# display.net
KiCad netlist of a schematic drawn in EAGLE
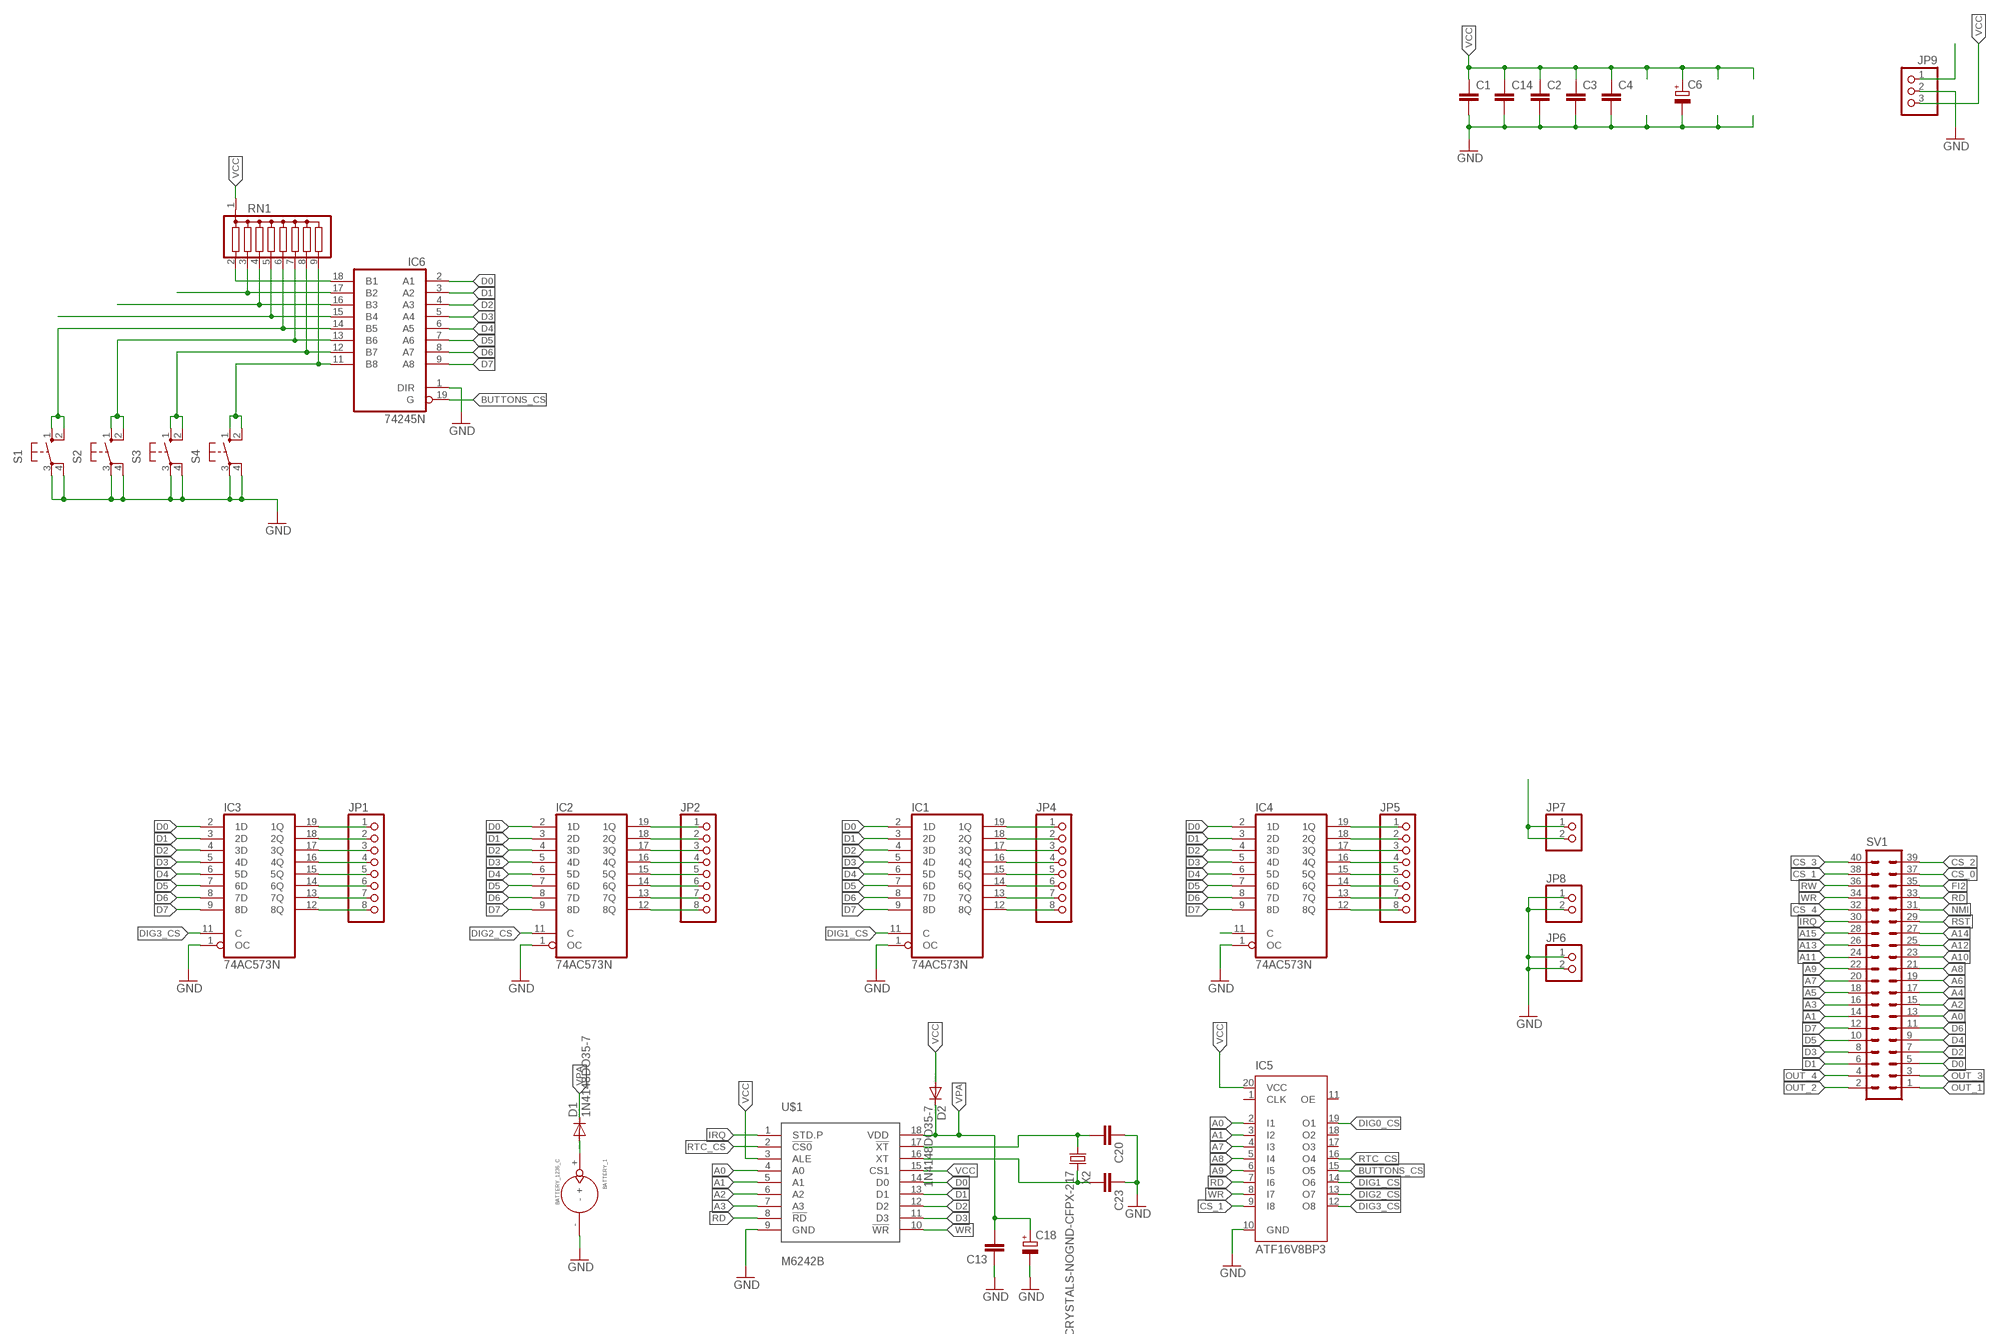
[diagram p0: schematic, sheet 1]

(export (version "E")
  (design (tool "Eeschema 10.0.6"))
  (components
    (comp (ref "BATTERY_1")
      (value "BATTERY_1236_C")
      (footprint "eagle-import:BATTERY_1236_C")
      (libsource (lib "eagle-import") (part "BATTERY_1236_C"))
    )
    (comp (ref "C1")
      (value "C-EUC1206")
      (footprint "eagle-import:C1206")
      (libsource (lib "eagle-import") (part "C-EUC1206"))
    )
    (comp (ref "C2")
      (value "C-EUC1206")
      (footprint "eagle-import:C1206")
      (libsource (lib "eagle-import") (part "C-EUC1206"))
    )
    (comp (ref "C3")
      (value "C-EUC1206")
      (footprint "eagle-import:C1206")
      (libsource (lib "eagle-import") (part "C-EUC1206"))
    )
    (comp (ref "C4")
      (value "C-EUC1206")
      (footprint "eagle-import:C1206")
      (libsource (lib "eagle-import") (part "C-EUC1206"))
    )
    (comp (ref "C6")
      (value "CPOL-EUSMCD")
      (footprint "eagle-import:SMC_D")
      (libsource (lib "eagle-import") (part "CPOL-EUSMCD"))
    )
    (comp (ref "C13")
      (value "C-EUC0603")
      (footprint "eagle-import:C0603")
      (libsource (lib "eagle-import") (part "C-EUC0603"))
    )
    (comp (ref "C14")
      (value "C-EUC1206")
      (footprint "eagle-import:C1206")
      (libsource (lib "eagle-import") (part "C-EUC1206"))
    )
    (comp (ref "C18")
      (value "CPOL-EUSMCB")
      (footprint "eagle-import:SMC_B")
      (libsource (lib "eagle-import") (part "CPOL-EUSMCB"))
    )
    (comp (ref "C20")
      (value "C-EUC0603")
      (footprint "eagle-import:C0603")
      (libsource (lib "eagle-import") (part "C-EUC0603"))
    )
    (comp (ref "C23")
      (value "C-EUC0603")
      (footprint "eagle-import:C0603")
      (libsource (lib "eagle-import") (part "C-EUC0603"))
    )
    (comp (ref "D1")
      (value "1N4148DO35-7")
      (footprint "eagle-import:DO35-7")
      (libsource (lib "eagle-import") (part "1N4148DO35-7"))
    )
    (comp (ref "D2")
      (value "1N4148DO35-7")
      (footprint "eagle-import:DO35-7")
      (libsource (lib "eagle-import") (part "1N4148DO35-7"))
    )
    (comp (ref "IC1")
      (value "74AC573N")
      (footprint "eagle-import:DIL20")
      (libsource (lib "eagle-import") (part "74573NAC"))
    )
    (comp (ref "IC2")
      (value "74AC573N")
      (footprint "eagle-import:DIL20")
      (libsource (lib "eagle-import") (part "74573NAC"))
    )
    (comp (ref "IC3")
      (value "74AC573N")
      (footprint "eagle-import:DIL20")
      (libsource (lib "eagle-import") (part "74573NAC"))
    )
    (comp (ref "IC4")
      (value "74AC573N")
      (footprint "eagle-import:DIL20")
      (libsource (lib "eagle-import") (part "74573NAC"))
    )
    (comp (ref "IC5")
      (value "ATF16V8BP3")
      (footprint "eagle-import:DIL20")
      (fields (field (name "MPN") "ATF16V8CZ-15PU"))
      (libsource (lib "eagle-import") (part "ATF16V8BP3"))
    )
    (comp (ref "IC6")
      (value "74245N")
      (footprint "eagle-import:DIL20")
      (libsource (lib "eagle-import") (part "74245NLS"))
    )
    (comp (ref "JP1")
      (value "PINHD-1X8")
      (footprint "eagle-import:1X08")
      (libsource (lib "eagle-import") (part "PINHD-1X8"))
    )
    (comp (ref "JP2")
      (value "PINHD-1X8")
      (footprint "eagle-import:1X08")
      (libsource (lib "eagle-import") (part "PINHD-1X8"))
    )
    (comp (ref "JP4")
      (value "PINHD-1X8")
      (footprint "eagle-import:1X08")
      (libsource (lib "eagle-import") (part "PINHD-1X8"))
    )
    (comp (ref "JP5")
      (value "PINHD-1X8")
      (footprint "eagle-import:1X08")
      (libsource (lib "eagle-import") (part "PINHD-1X8"))
    )
    (comp (ref "JP6")
      (value "PINHD-1X2")
      (footprint "eagle-import:1X02")
      (libsource (lib "eagle-import") (part "PINHD-1X2"))
    )
    (comp (ref "JP7")
      (value "PINHD-1X2")
      (footprint "eagle-import:1X02")
      (libsource (lib "eagle-import") (part "PINHD-1X2"))
    )
    (comp (ref "JP8")
      (value "PINHD-1X2")
      (footprint "eagle-import:1X02")
      (libsource (lib "eagle-import") (part "PINHD-1X2"))
    )
    (comp (ref "JP9")
      (value "PINHD-1X3/90")
      (footprint "eagle-import:1X03_90")
      (libsource (lib "eagle-import") (part "PINHD-1X3/90"))
    )
    (comp (ref "RN1")
      (value "G08R")
      (footprint "eagle-import:SIL9")
      (libsource (lib "eagle-import") (part "G08R"))
    )
    (comp (ref "S1")
      (value "40-XX")
      (footprint "eagle-import:B3F-40XX")
      (fields (field (name "MF") "OMRON COMPONENTS USA") (field (name "MPN") "B3F-4000"))
      (libsource (lib "eagle-import") (part "40-XX"))
    )
    (comp (ref "S2")
      (value "40-XX")
      (footprint "eagle-import:B3F-40XX")
      (fields (field (name "MF") "OMRON COMPONENTS USA") (field (name "MPN") "B3F-4000"))
      (libsource (lib "eagle-import") (part "40-XX"))
    )
    (comp (ref "S3")
      (value "40-XX")
      (footprint "eagle-import:B3F-40XX")
      (fields (field (name "MF") "OMRON COMPONENTS USA") (field (name "MPN") "B3F-4000"))
      (libsource (lib "eagle-import") (part "40-XX"))
    )
    (comp (ref "S4")
      (value "40-XX")
      (footprint "eagle-import:B3F-40XX")
      (fields (field (name "MF") "OMRON COMPONENTS USA") (field (name "MPN") "B3F-4000"))
      (libsource (lib "eagle-import") (part "40-XX"))
    )
    (comp (ref "SV1")
      (value "ML40L")
      (footprint "eagle-import:ML40L")
      (libsource (lib "eagle-import") (part "ML40L"))
    )
    (comp (ref "U$1")
      (value "M6242B")
      (footprint "eagle-import:DIL18")
      (libsource (lib "eagle-import") (part "M6242B"))
    )
    (comp (ref "X2")
      (value "CRYSTALS-NOGND-CFPX-217")
      (footprint "eagle-import:3.2X1.5-2-PAD")
      (libsource (lib "eagle-import") (part "CRYSTALS-NOGND-CFPX-217"))
    )
  )
  (nets
    (net (code "1") (name "/9V") (class "Default")
      (node (ref "JP7") (pin "1") (pinfunction "1_1") (pintype "passive"))
      (node (ref "JP7") (pin "2") (pinfunction "2_2") (pintype "passive"))
      (node (ref "JP9") (pin "1") (pinfunction "1_1") (pintype "passive"))
    )
    (net (code "2") (name "A0") (class "Default")
      (node (ref "IC5") (pin "2") (pinfunction "I1_2") (pintype "input"))
      (node (ref "SV1") (pin "13") (pinfunction "13_13") (pintype "passive"))
      (node (ref "U$1") (pin "4") (pinfunction "A0_4") (pintype "bidirectional"))
    )
    (net (code "3") (name "A1") (class "Default")
      (node (ref "IC5") (pin "3") (pinfunction "I2_3") (pintype "input"))
      (node (ref "SV1") (pin "14") (pinfunction "14_14") (pintype "passive"))
      (node (ref "U$1") (pin "5") (pinfunction "A1_5") (pintype "bidirectional"))
    )
    (net (code "4") (name "A2") (class "Default")
      (node (ref "SV1") (pin "15") (pinfunction "15_15") (pintype "passive"))
      (node (ref "U$1") (pin "6") (pinfunction "A2_6") (pintype "bidirectional"))
    )
    (net (code "5") (name "A3") (class "Default")
      (node (ref "SV1") (pin "16") (pinfunction "16_16") (pintype "passive"))
      (node (ref "U$1") (pin "7") (pinfunction "A3_7") (pintype "bidirectional"))
    )
    (net (code "6") (name "A4") (class "Default")
      (node (ref "SV1") (pin "17") (pinfunction "17_17") (pintype "passive"))
    )
    (net (code "7") (name "A5") (class "Default")
      (node (ref "SV1") (pin "18") (pinfunction "18_18") (pintype "passive"))
    )
    (net (code "8") (name "A6") (class "Default")
      (node (ref "SV1") (pin "19") (pinfunction "19_19") (pintype "passive"))
    )
    (net (code "9") (name "A7") (class "Default")
      (node (ref "IC5") (pin "4") (pinfunction "I3_4") (pintype "input"))
      (node (ref "SV1") (pin "20") (pinfunction "20_20") (pintype "passive"))
    )
    (net (code "10") (name "A8") (class "Default")
      (node (ref "IC5") (pin "5") (pinfunction "I4_5") (pintype "input"))
      (node (ref "SV1") (pin "21") (pinfunction "21_21") (pintype "passive"))
    )
    (net (code "11") (name "A9") (class "Default")
      (node (ref "IC5") (pin "6") (pinfunction "I5_6") (pintype "input"))
      (node (ref "SV1") (pin "22") (pinfunction "22_22") (pintype "passive"))
    )
    (net (code "12") (name "A10") (class "Default")
      (node (ref "SV1") (pin "23") (pinfunction "23_23") (pintype "passive"))
    )
    (net (code "13") (name "A11") (class "Default")
      (node (ref "SV1") (pin "24") (pinfunction "24_24") (pintype "passive"))
    )
    (net (code "14") (name "A12") (class "Default")
      (node (ref "SV1") (pin "25") (pinfunction "25_25") (pintype "passive"))
    )
    (net (code "15") (name "A13") (class "Default")
      (node (ref "SV1") (pin "26") (pinfunction "26_26") (pintype "passive"))
    )
    (net (code "16") (name "A14") (class "Default")
      (node (ref "SV1") (pin "27") (pinfunction "27_27") (pintype "passive"))
    )
    (net (code "17") (name "A15") (class "Default")
      (node (ref "SV1") (pin "28") (pinfunction "28_28") (pintype "passive"))
    )
    (net (code "18") (name "BUTTONS_CS") (class "Default")
      (node (ref "IC5") (pin "15") (pinfunction "O5_15") (pintype "output"))
      (node (ref "IC6") (pin "19") (pinfunction "G_19") (pintype "input"))
    )
    (net (code "19") (name "CS_0") (class "Default")
      (node (ref "SV1") (pin "37") (pinfunction "37_37") (pintype "passive"))
    )
    (net (code "20") (name "CS_1") (class "Default")
      (node (ref "IC5") (pin "9") (pinfunction "I8_9") (pintype "input"))
      (node (ref "SV1") (pin "38") (pinfunction "38_38") (pintype "passive"))
    )
    (net (code "21") (name "CS_2") (class "Default")
      (node (ref "SV1") (pin "39") (pinfunction "39_39") (pintype "passive"))
    )
    (net (code "22") (name "CS_3") (class "Default")
      (node (ref "SV1") (pin "40") (pinfunction "40_40") (pintype "passive"))
    )
    (net (code "23") (name "CS_4") (class "Default")
      (node (ref "SV1") (pin "32") (pinfunction "32_32") (pintype "passive"))
    )
    (net (code "24") (name "D0") (class "Default")
      (node (ref "IC1") (pin "2") (pinfunction "1D_2") (pintype "input"))
      (node (ref "IC2") (pin "2") (pinfunction "1D_2") (pintype "input"))
      (node (ref "IC3") (pin "2") (pinfunction "1D_2") (pintype "input"))
      (node (ref "IC4") (pin "2") (pinfunction "1D_2") (pintype "input"))
      (node (ref "IC6") (pin "2") (pinfunction "A1_2") (pintype "bidirectional"))
      (node (ref "SV1") (pin "5") (pinfunction "5_5") (pintype "passive"))
      (node (ref "U$1") (pin "14") (pinfunction "D0_14") (pintype "bidirectional"))
    )
    (net (code "25") (name "D1") (class "Default")
      (node (ref "IC1") (pin "3") (pinfunction "2D_3") (pintype "input"))
      (node (ref "IC2") (pin "3") (pinfunction "2D_3") (pintype "input"))
      (node (ref "IC3") (pin "3") (pinfunction "2D_3") (pintype "input"))
      (node (ref "IC4") (pin "3") (pinfunction "2D_3") (pintype "input"))
      (node (ref "IC6") (pin "3") (pinfunction "A2_3") (pintype "bidirectional"))
      (node (ref "SV1") (pin "6") (pinfunction "6_6") (pintype "passive"))
      (node (ref "U$1") (pin "13") (pinfunction "D1_13") (pintype "bidirectional"))
    )
    (net (code "26") (name "D2") (class "Default")
      (node (ref "IC1") (pin "4") (pinfunction "3D_4") (pintype "input"))
      (node (ref "IC2") (pin "4") (pinfunction "3D_4") (pintype "input"))
      (node (ref "IC3") (pin "4") (pinfunction "3D_4") (pintype "input"))
      (node (ref "IC4") (pin "4") (pinfunction "3D_4") (pintype "input"))
      (node (ref "IC6") (pin "4") (pinfunction "A3_4") (pintype "bidirectional"))
      (node (ref "SV1") (pin "7") (pinfunction "7_7") (pintype "passive"))
      (node (ref "U$1") (pin "12") (pinfunction "D2_12") (pintype "bidirectional"))
    )
    (net (code "27") (name "D3") (class "Default")
      (node (ref "IC1") (pin "5") (pinfunction "4D_5") (pintype "input"))
      (node (ref "IC2") (pin "5") (pinfunction "4D_5") (pintype "input"))
      (node (ref "IC3") (pin "5") (pinfunction "4D_5") (pintype "input"))
      (node (ref "IC4") (pin "5") (pinfunction "4D_5") (pintype "input"))
      (node (ref "IC6") (pin "5") (pinfunction "A4_5") (pintype "bidirectional"))
      (node (ref "SV1") (pin "8") (pinfunction "8_8") (pintype "passive"))
      (node (ref "U$1") (pin "11") (pinfunction "D3_11") (pintype "bidirectional"))
    )
    (net (code "28") (name "D4") (class "Default")
      (node (ref "IC1") (pin "6") (pinfunction "5D_6") (pintype "input"))
      (node (ref "IC2") (pin "6") (pinfunction "5D_6") (pintype "input"))
      (node (ref "IC3") (pin "6") (pinfunction "5D_6") (pintype "input"))
      (node (ref "IC4") (pin "6") (pinfunction "5D_6") (pintype "input"))
      (node (ref "IC6") (pin "6") (pinfunction "A5_6") (pintype "bidirectional"))
      (node (ref "SV1") (pin "9") (pinfunction "9_9") (pintype "passive"))
    )
    (net (code "29") (name "D5") (class "Default")
      (node (ref "IC1") (pin "7") (pinfunction "6D_7") (pintype "input"))
      (node (ref "IC2") (pin "7") (pinfunction "6D_7") (pintype "input"))
      (node (ref "IC3") (pin "7") (pinfunction "6D_7") (pintype "input"))
      (node (ref "IC4") (pin "7") (pinfunction "6D_7") (pintype "input"))
      (node (ref "IC6") (pin "7") (pinfunction "A6_7") (pintype "bidirectional"))
      (node (ref "SV1") (pin "10") (pinfunction "10_10") (pintype "passive"))
    )
    (net (code "30") (name "D6") (class "Default")
      (node (ref "IC1") (pin "8") (pinfunction "7D_8") (pintype "input"))
      (node (ref "IC2") (pin "8") (pinfunction "7D_8") (pintype "input"))
      (node (ref "IC3") (pin "8") (pinfunction "7D_8") (pintype "input"))
      (node (ref "IC4") (pin "8") (pinfunction "7D_8") (pintype "input"))
      (node (ref "IC6") (pin "8") (pinfunction "A7_8") (pintype "bidirectional"))
      (node (ref "SV1") (pin "11") (pinfunction "11_11") (pintype "passive"))
    )
    (net (code "31") (name "D7") (class "Default")
      (node (ref "IC1") (pin "9") (pinfunction "8D_9") (pintype "input"))
      (node (ref "IC2") (pin "9") (pinfunction "8D_9") (pintype "input"))
      (node (ref "IC3") (pin "9") (pinfunction "8D_9") (pintype "input"))
      (node (ref "IC4") (pin "9") (pinfunction "8D_9") (pintype "input"))
      (node (ref "IC6") (pin "9") (pinfunction "A8_9") (pintype "bidirectional"))
      (node (ref "SV1") (pin "12") (pinfunction "12_12") (pintype "passive"))
    )
    (net (code "32") (name "DIG0_CS") (class "Default")
      (node (ref "IC4") (pin "11") (pinfunction "C_11") (pintype "input"))
      (node (ref "IC5") (pin "19") (pinfunction "O1_19") (pintype "output"))
    )
    (net (code "33") (name "DIG1_CS") (class "Default")
      (node (ref "IC1") (pin "11") (pinfunction "C_11") (pintype "input"))
      (node (ref "IC5") (pin "14") (pinfunction "O6_14") (pintype "output"))
    )
    (net (code "34") (name "DIG2_CS") (class "Default")
      (node (ref "IC2") (pin "11") (pinfunction "C_11") (pintype "input"))
      (node (ref "IC5") (pin "13") (pinfunction "O7_13") (pintype "output"))
    )
    (net (code "35") (name "DIG3_CS") (class "Default")
      (node (ref "IC3") (pin "11") (pinfunction "C_11") (pintype "input"))
      (node (ref "IC5") (pin "12") (pinfunction "O8_12") (pintype "output"))
    )
    (net (code "36") (name "FI2") (class "Default")
      (node (ref "SV1") (pin "35") (pinfunction "35_35") (pintype "passive"))
    )
    (net (code "37") (name "GND") (class "Default")
      (node (ref "BATTERY_1") (pin "-") (pinfunction "-_-") (pintype "bidirectional"))
      (node (ref "C1") (pin "2") (pinfunction "2_2") (pintype "passive"))
      (node (ref "C13") (pin "1") (pinfunction "1_1") (pintype "passive"))
      (node (ref "C14") (pin "2") (pinfunction "2_2") (pintype "passive"))
      (node (ref "C18") (pin "-") (pinfunction "-_-") (pintype "passive"))
      (node (ref "C2") (pin "2") (pinfunction "2_2") (pintype "passive"))
      (node (ref "C20") (pin "1") (pinfunction "1_1") (pintype "passive"))
      (node (ref "C23") (pin "1") (pinfunction "1_1") (pintype "passive"))
      (node (ref "C3") (pin "2") (pinfunction "2_2") (pintype "passive"))
      (node (ref "C4") (pin "2") (pinfunction "2_2") (pintype "passive"))
      (node (ref "C6") (pin "-") (pinfunction "-_-") (pintype "passive"))
      (node (ref "IC1") (pin "1") (pinfunction "OC_1") (pintype "input"))
      (node (ref "IC2") (pin "1") (pinfunction "OC_1") (pintype "input"))
      (node (ref "IC3") (pin "1") (pinfunction "OC_1") (pintype "input"))
      (node (ref "IC4") (pin "1") (pinfunction "OC_1") (pintype "input"))
      (node (ref "IC5") (pin "10") (pinfunction "GND_10") (pintype "power_in"))
      (node (ref "IC6") (pin "1") (pinfunction "DIR_1") (pintype "input"))
      (node (ref "JP6") (pin "1") (pinfunction "1_1") (pintype "passive"))
      (node (ref "JP6") (pin "2") (pinfunction "2_2") (pintype "passive"))
      (node (ref "JP8") (pin "1") (pinfunction "1_1") (pintype "passive"))
      (node (ref "JP8") (pin "2") (pinfunction "2_2") (pintype "passive"))
      (node (ref "JP9") (pin "2") (pinfunction "2_2") (pintype "passive"))
      (node (ref "S1") (pin "3") (pinfunction "P_3") (pintype "passive"))
      (node (ref "S1") (pin "4") (pinfunction "P1_4") (pintype "passive"))
      (node (ref "S2") (pin "3") (pinfunction "P_3") (pintype "passive"))
      (node (ref "S2") (pin "4") (pinfunction "P1_4") (pintype "passive"))
      (node (ref "S3") (pin "3") (pinfunction "P_3") (pintype "passive"))
      (node (ref "S3") (pin "4") (pinfunction "P1_4") (pintype "passive"))
      (node (ref "S4") (pin "3") (pinfunction "P_3") (pintype "passive"))
      (node (ref "S4") (pin "4") (pinfunction "P1_4") (pintype "passive"))
      (node (ref "U$1") (pin "9") (pinfunction "GND_9") (pintype "bidirectional"))
    )
    (net (code "38") (name "IRQ") (class "Default")
      (node (ref "SV1") (pin "30") (pinfunction "30_30") (pintype "passive"))
      (node (ref "U$1") (pin "1") (pinfunction "STD.P_1") (pintype "bidirectional"))
    )
    (net (code "39") (name "NMI") (class "Default")
      (node (ref "SV1") (pin "31") (pinfunction "31_31") (pintype "passive"))
    )
    (net (code "40") (name "Net-(BATTERY_1-Pad+)") (class "Default")
      (node (ref "BATTERY_1") (pin "+") (pinfunction "+_+") (pintype "bidirectional"))
      (node (ref "D1") (pin "A") (pinfunction "A_A") (pintype "passive"))
    )
    (net (code "41") (name "Net-(IC1A-1Q)") (class "Default")
      (node (ref "IC1") (pin "19") (pinfunction "1Q_19") (pintype "tri_state"))
      (node (ref "JP4") (pin "1") (pinfunction "1_1") (pintype "passive"))
    )
    (net (code "42") (name "Net-(IC1A-2Q)") (class "Default")
      (node (ref "IC1") (pin "18") (pinfunction "2Q_18") (pintype "tri_state"))
      (node (ref "JP4") (pin "2") (pinfunction "2_2") (pintype "passive"))
    )
    (net (code "43") (name "Net-(IC1A-3Q)") (class "Default")
      (node (ref "IC1") (pin "17") (pinfunction "3Q_17") (pintype "tri_state"))
      (node (ref "JP4") (pin "3") (pinfunction "3_3") (pintype "passive"))
    )
    (net (code "44") (name "Net-(IC1A-4Q)") (class "Default")
      (node (ref "IC1") (pin "16") (pinfunction "4Q_16") (pintype "tri_state"))
      (node (ref "JP4") (pin "4") (pinfunction "4_4") (pintype "passive"))
    )
    (net (code "45") (name "Net-(IC1A-5Q)") (class "Default")
      (node (ref "IC1") (pin "15") (pinfunction "5Q_15") (pintype "tri_state"))
      (node (ref "JP4") (pin "5") (pinfunction "5_5") (pintype "passive"))
    )
    (net (code "46") (name "Net-(IC1A-6Q)") (class "Default")
      (node (ref "IC1") (pin "14") (pinfunction "6Q_14") (pintype "tri_state"))
      (node (ref "JP4") (pin "6") (pinfunction "6_6") (pintype "passive"))
    )
    (net (code "47") (name "Net-(IC1A-7Q)") (class "Default")
      (node (ref "IC1") (pin "13") (pinfunction "7Q_13") (pintype "tri_state"))
      (node (ref "JP4") (pin "7") (pinfunction "7_7") (pintype "passive"))
    )
    (net (code "48") (name "Net-(IC1A-8Q)") (class "Default")
      (node (ref "IC1") (pin "12") (pinfunction "8Q_12") (pintype "tri_state"))
      (node (ref "JP4") (pin "8") (pinfunction "8_8") (pintype "passive"))
    )
    (net (code "49") (name "Net-(IC2A-1Q)") (class "Default")
      (node (ref "IC2") (pin "19") (pinfunction "1Q_19") (pintype "tri_state"))
      (node (ref "JP2") (pin "1") (pinfunction "1_1") (pintype "passive"))
    )
    (net (code "50") (name "Net-(IC2A-2Q)") (class "Default")
      (node (ref "IC2") (pin "18") (pinfunction "2Q_18") (pintype "tri_state"))
      (node (ref "JP2") (pin "2") (pinfunction "2_2") (pintype "passive"))
    )
    (net (code "51") (name "Net-(IC2A-3Q)") (class "Default")
      (node (ref "IC2") (pin "17") (pinfunction "3Q_17") (pintype "tri_state"))
      (node (ref "JP2") (pin "3") (pinfunction "3_3") (pintype "passive"))
    )
    (net (code "52") (name "Net-(IC2A-4Q)") (class "Default")
      (node (ref "IC2") (pin "16") (pinfunction "4Q_16") (pintype "tri_state"))
      (node (ref "JP2") (pin "4") (pinfunction "4_4") (pintype "passive"))
    )
    (net (code "53") (name "Net-(IC2A-5Q)") (class "Default")
      (node (ref "IC2") (pin "15") (pinfunction "5Q_15") (pintype "tri_state"))
      (node (ref "JP2") (pin "5") (pinfunction "5_5") (pintype "passive"))
    )
    (net (code "54") (name "Net-(IC2A-6Q)") (class "Default")
      (node (ref "IC2") (pin "14") (pinfunction "6Q_14") (pintype "tri_state"))
      (node (ref "JP2") (pin "6") (pinfunction "6_6") (pintype "passive"))
    )
    (net (code "55") (name "Net-(IC2A-7Q)") (class "Default")
      (node (ref "IC2") (pin "13") (pinfunction "7Q_13") (pintype "tri_state"))
      (node (ref "JP2") (pin "7") (pinfunction "7_7") (pintype "passive"))
    )
    (net (code "56") (name "Net-(IC2A-8Q)") (class "Default")
      (node (ref "IC2") (pin "12") (pinfunction "8Q_12") (pintype "tri_state"))
      (node (ref "JP2") (pin "8") (pinfunction "8_8") (pintype "passive"))
    )
    (net (code "57") (name "Net-(IC3A-1Q)") (class "Default")
      (node (ref "IC3") (pin "19") (pinfunction "1Q_19") (pintype "tri_state"))
      (node (ref "JP1") (pin "1") (pinfunction "1_1") (pintype "passive"))
    )
    (net (code "58") (name "Net-(IC3A-2Q)") (class "Default")
      (node (ref "IC3") (pin "18") (pinfunction "2Q_18") (pintype "tri_state"))
      (node (ref "JP1") (pin "2") (pinfunction "2_2") (pintype "passive"))
    )
    (net (code "59") (name "Net-(IC3A-3Q)") (class "Default")
      (node (ref "IC3") (pin "17") (pinfunction "3Q_17") (pintype "tri_state"))
      (node (ref "JP1") (pin "3") (pinfunction "3_3") (pintype "passive"))
    )
    (net (code "60") (name "Net-(IC3A-4Q)") (class "Default")
      (node (ref "IC3") (pin "16") (pinfunction "4Q_16") (pintype "tri_state"))
      (node (ref "JP1") (pin "4") (pinfunction "4_4") (pintype "passive"))
    )
    (net (code "61") (name "Net-(IC3A-5Q)") (class "Default")
      (node (ref "IC3") (pin "15") (pinfunction "5Q_15") (pintype "tri_state"))
      (node (ref "JP1") (pin "5") (pinfunction "5_5") (pintype "passive"))
    )
    (net (code "62") (name "Net-(IC3A-6Q)") (class "Default")
      (node (ref "IC3") (pin "14") (pinfunction "6Q_14") (pintype "tri_state"))
      (node (ref "JP1") (pin "6") (pinfunction "6_6") (pintype "passive"))
    )
    (net (code "63") (name "Net-(IC3A-7Q)") (class "Default")
      (node (ref "IC3") (pin "13") (pinfunction "7Q_13") (pintype "tri_state"))
      (node (ref "JP1") (pin "7") (pinfunction "7_7") (pintype "passive"))
    )
    (net (code "64") (name "Net-(IC3A-8Q)") (class "Default")
      (node (ref "IC3") (pin "12") (pinfunction "8Q_12") (pintype "tri_state"))
      (node (ref "JP1") (pin "8") (pinfunction "8_8") (pintype "passive"))
    )
    (net (code "65") (name "Net-(IC4A-1Q)") (class "Default")
      (node (ref "IC4") (pin "19") (pinfunction "1Q_19") (pintype "tri_state"))
      (node (ref "JP5") (pin "1") (pinfunction "1_1") (pintype "passive"))
    )
    (net (code "66") (name "Net-(IC4A-2Q)") (class "Default")
      (node (ref "IC4") (pin "18") (pinfunction "2Q_18") (pintype "tri_state"))
      (node (ref "JP5") (pin "2") (pinfunction "2_2") (pintype "passive"))
    )
    (net (code "67") (name "Net-(IC4A-3Q)") (class "Default")
      (node (ref "IC4") (pin "17") (pinfunction "3Q_17") (pintype "tri_state"))
      (node (ref "JP5") (pin "3") (pinfunction "3_3") (pintype "passive"))
    )
    (net (code "68") (name "Net-(IC4A-4Q)") (class "Default")
      (node (ref "IC4") (pin "16") (pinfunction "4Q_16") (pintype "tri_state"))
      (node (ref "JP5") (pin "4") (pinfunction "4_4") (pintype "passive"))
    )
    (net (code "69") (name "Net-(IC4A-5Q)") (class "Default")
      (node (ref "IC4") (pin "15") (pinfunction "5Q_15") (pintype "tri_state"))
      (node (ref "JP5") (pin "5") (pinfunction "5_5") (pintype "passive"))
    )
    (net (code "70") (name "Net-(IC4A-6Q)") (class "Default")
      (node (ref "IC4") (pin "14") (pinfunction "6Q_14") (pintype "tri_state"))
      (node (ref "JP5") (pin "6") (pinfunction "6_6") (pintype "passive"))
    )
    (net (code "71") (name "Net-(IC4A-7Q)") (class "Default")
      (node (ref "IC4") (pin "13") (pinfunction "7Q_13") (pintype "tri_state"))
      (node (ref "JP5") (pin "7") (pinfunction "7_7") (pintype "passive"))
    )
    (net (code "72") (name "Net-(IC4A-8Q)") (class "Default")
      (node (ref "IC4") (pin "12") (pinfunction "8Q_12") (pintype "tri_state"))
      (node (ref "JP5") (pin "8") (pinfunction "8_8") (pintype "passive"))
    )
    (net (code "73") (name "Net-(IC6A-B1)") (class "Default")
      (node (ref "IC6") (pin "18") (pinfunction "B1_18") (pintype "bidirectional"))
      (node (ref "RN1") (pin "2") (pinfunction "2_2") (pintype "passive"))
    )
    (net (code "74") (name "Net-(IC6A-B2)") (class "Default")
      (node (ref "IC6") (pin "17") (pinfunction "B2_17") (pintype "bidirectional"))
      (node (ref "RN1") (pin "3") (pinfunction "3_3") (pintype "passive"))
    )
    (net (code "75") (name "Net-(IC6A-B3)") (class "Default")
      (node (ref "IC6") (pin "16") (pinfunction "B3_16") (pintype "bidirectional"))
      (node (ref "RN1") (pin "4") (pinfunction "4_4") (pintype "passive"))
    )
    (net (code "76") (name "Net-(IC6A-B4)") (class "Default")
      (node (ref "IC6") (pin "15") (pinfunction "B4_15") (pintype "bidirectional"))
      (node (ref "RN1") (pin "5") (pinfunction "5_5") (pintype "passive"))
    )
    (net (code "77") (name "Net-(IC6A-B5)") (class "Default")
      (node (ref "IC6") (pin "14") (pinfunction "B5_14") (pintype "bidirectional"))
      (node (ref "RN1") (pin "6") (pinfunction "6_6") (pintype "passive"))
      (node (ref "S1") (pin "1") (pinfunction "S_1") (pintype "passive"))
      (node (ref "S1") (pin "2") (pinfunction "S1_2") (pintype "passive"))
    )
    (net (code "78") (name "Net-(IC6A-B6)") (class "Default")
      (node (ref "IC6") (pin "13") (pinfunction "B6_13") (pintype "bidirectional"))
      (node (ref "RN1") (pin "7") (pinfunction "7_7") (pintype "passive"))
      (node (ref "S2") (pin "1") (pinfunction "S_1") (pintype "passive"))
      (node (ref "S2") (pin "2") (pinfunction "S1_2") (pintype "passive"))
    )
    (net (code "79") (name "Net-(IC6A-B7)") (class "Default")
      (node (ref "IC6") (pin "12") (pinfunction "B7_12") (pintype "bidirectional"))
      (node (ref "RN1") (pin "8") (pinfunction "8_8") (pintype "passive"))
      (node (ref "S3") (pin "1") (pinfunction "S_1") (pintype "passive"))
      (node (ref "S3") (pin "2") (pinfunction "S1_2") (pintype "passive"))
    )
    (net (code "80") (name "Net-(IC6A-B8)") (class "Default")
      (node (ref "IC6") (pin "11") (pinfunction "B8_11") (pintype "bidirectional"))
      (node (ref "RN1") (pin "9") (pinfunction "9_9") (pintype "passive"))
      (node (ref "S4") (pin "1") (pinfunction "S_1") (pintype "passive"))
      (node (ref "S4") (pin "2") (pinfunction "S1_2") (pintype "passive"))
    )
    (net (code "81") (name "Net-(U$1-XT)") (class "Default")
      (node (ref "C23") (pin "2") (pinfunction "2_2") (pintype "passive"))
      (node (ref "U$1") (pin "16") (pinfunction "XT_16") (pintype "bidirectional"))
      (node (ref "X2") (pin "2") (pinfunction "2_2") (pintype "passive"))
    )
    (net (code "82") (name "Net-(U$1-~{XT})") (class "Default")
      (node (ref "C20") (pin "2") (pinfunction "2_2") (pintype "passive"))
      (node (ref "U$1") (pin "17") (pinfunction "~{XT}_17") (pintype "bidirectional"))
      (node (ref "X2") (pin "1") (pinfunction "1_1") (pintype "passive"))
    )
    (net (code "83") (name "OUT_1") (class "Default")
      (node (ref "SV1") (pin "1") (pinfunction "1_1") (pintype "passive"))
    )
    (net (code "84") (name "OUT_2") (class "Default")
      (node (ref "SV1") (pin "2") (pinfunction "2_2") (pintype "passive"))
    )
    (net (code "85") (name "OUT_3") (class "Default")
      (node (ref "SV1") (pin "3") (pinfunction "3_3") (pintype "passive"))
    )
    (net (code "86") (name "OUT_4") (class "Default")
      (node (ref "SV1") (pin "4") (pinfunction "4_4") (pintype "passive"))
    )
    (net (code "87") (name "RD") (class "Default")
      (node (ref "IC5") (pin "7") (pinfunction "I6_7") (pintype "input"))
      (node (ref "SV1") (pin "33") (pinfunction "33_33") (pintype "passive"))
      (node (ref "U$1") (pin "8") (pinfunction "~{RD}_8") (pintype "bidirectional"))
    )
    (net (code "88") (name "RST") (class "Default")
      (node (ref "SV1") (pin "29") (pinfunction "29_29") (pintype "passive"))
    )
    (net (code "89") (name "RTC_CS") (class "Default")
      (node (ref "IC5") (pin "16") (pinfunction "O4_16") (pintype "output"))
      (node (ref "U$1") (pin "2") (pinfunction "~{CS0}_2") (pintype "bidirectional"))
    )
    (net (code "90") (name "RW") (class "Default")
      (node (ref "SV1") (pin "36") (pinfunction "36_36") (pintype "passive"))
    )
    (net (code "91") (name "VCC") (class "Default")
      (node (ref "C1") (pin "1") (pinfunction "1_1") (pintype "passive"))
      (node (ref "C14") (pin "1") (pinfunction "1_1") (pintype "passive"))
      (node (ref "C2") (pin "1") (pinfunction "1_1") (pintype "passive"))
      (node (ref "C3") (pin "1") (pinfunction "1_1") (pintype "passive"))
      (node (ref "C4") (pin "1") (pinfunction "1_1") (pintype "passive"))
      (node (ref "C6") (pin "+") (pinfunction "+_+") (pintype "passive"))
      (node (ref "D2") (pin "A") (pinfunction "A_A") (pintype "passive"))
      (node (ref "IC5") (pin "20") (pinfunction "VCC_20") (pintype "power_in"))
      (node (ref "JP9") (pin "3") (pinfunction "3_3") (pintype "passive"))
      (node (ref "RN1") (pin "1") (pinfunction "1_1") (pintype "passive"))
      (node (ref "U$1") (pin "15") (pinfunction "CS1_15") (pintype "bidirectional"))
      (node (ref "U$1") (pin "3") (pinfunction "ALE_3") (pintype "bidirectional"))
    )
    (net (code "92") (name "VPA") (class "Default")
      (node (ref "C13") (pin "2") (pinfunction "2_2") (pintype "passive"))
      (node (ref "C18") (pin "+") (pinfunction "+_+") (pintype "passive"))
      (node (ref "D1") (pin "C") (pinfunction "C_C") (pintype "passive"))
      (node (ref "D2") (pin "C") (pinfunction "C_C") (pintype "passive"))
      (node (ref "U$1") (pin "18") (pinfunction "VDD_18") (pintype "bidirectional"))
    )
    (net (code "93") (name "WR") (class "Default")
      (node (ref "IC5") (pin "8") (pinfunction "I7_8") (pintype "input"))
      (node (ref "SV1") (pin "34") (pinfunction "34_34") (pintype "passive"))
      (node (ref "U$1") (pin "10") (pinfunction "~{WR}_10") (pintype "bidirectional"))
    )
    (net (code "94") (name "unconnected-(IC5-CLK-Pad1)") (class "Default")
      (node (ref "IC5") (pin "1") (pinfunction "CLK_1") (pintype "input"))
    )
    (net (code "95") (name "unconnected-(IC5-O2-Pad18)") (class "Default")
      (node (ref "IC5") (pin "18") (pinfunction "O2_18") (pintype "output"))
    )
    (net (code "96") (name "unconnected-(IC5-O3-Pad17)") (class "Default")
      (node (ref "IC5") (pin "17") (pinfunction "O3_17") (pintype "output"))
    )
    (net (code "97") (name "unconnected-(IC5-OE-Pad11)") (class "Default")
      (node (ref "IC5") (pin "11") (pinfunction "OE_11") (pintype "input"))
    )
  )
)
